# AudioXtreamer_Ymh01x.net
KiCad netlist of a schematic drawn in EAGLE
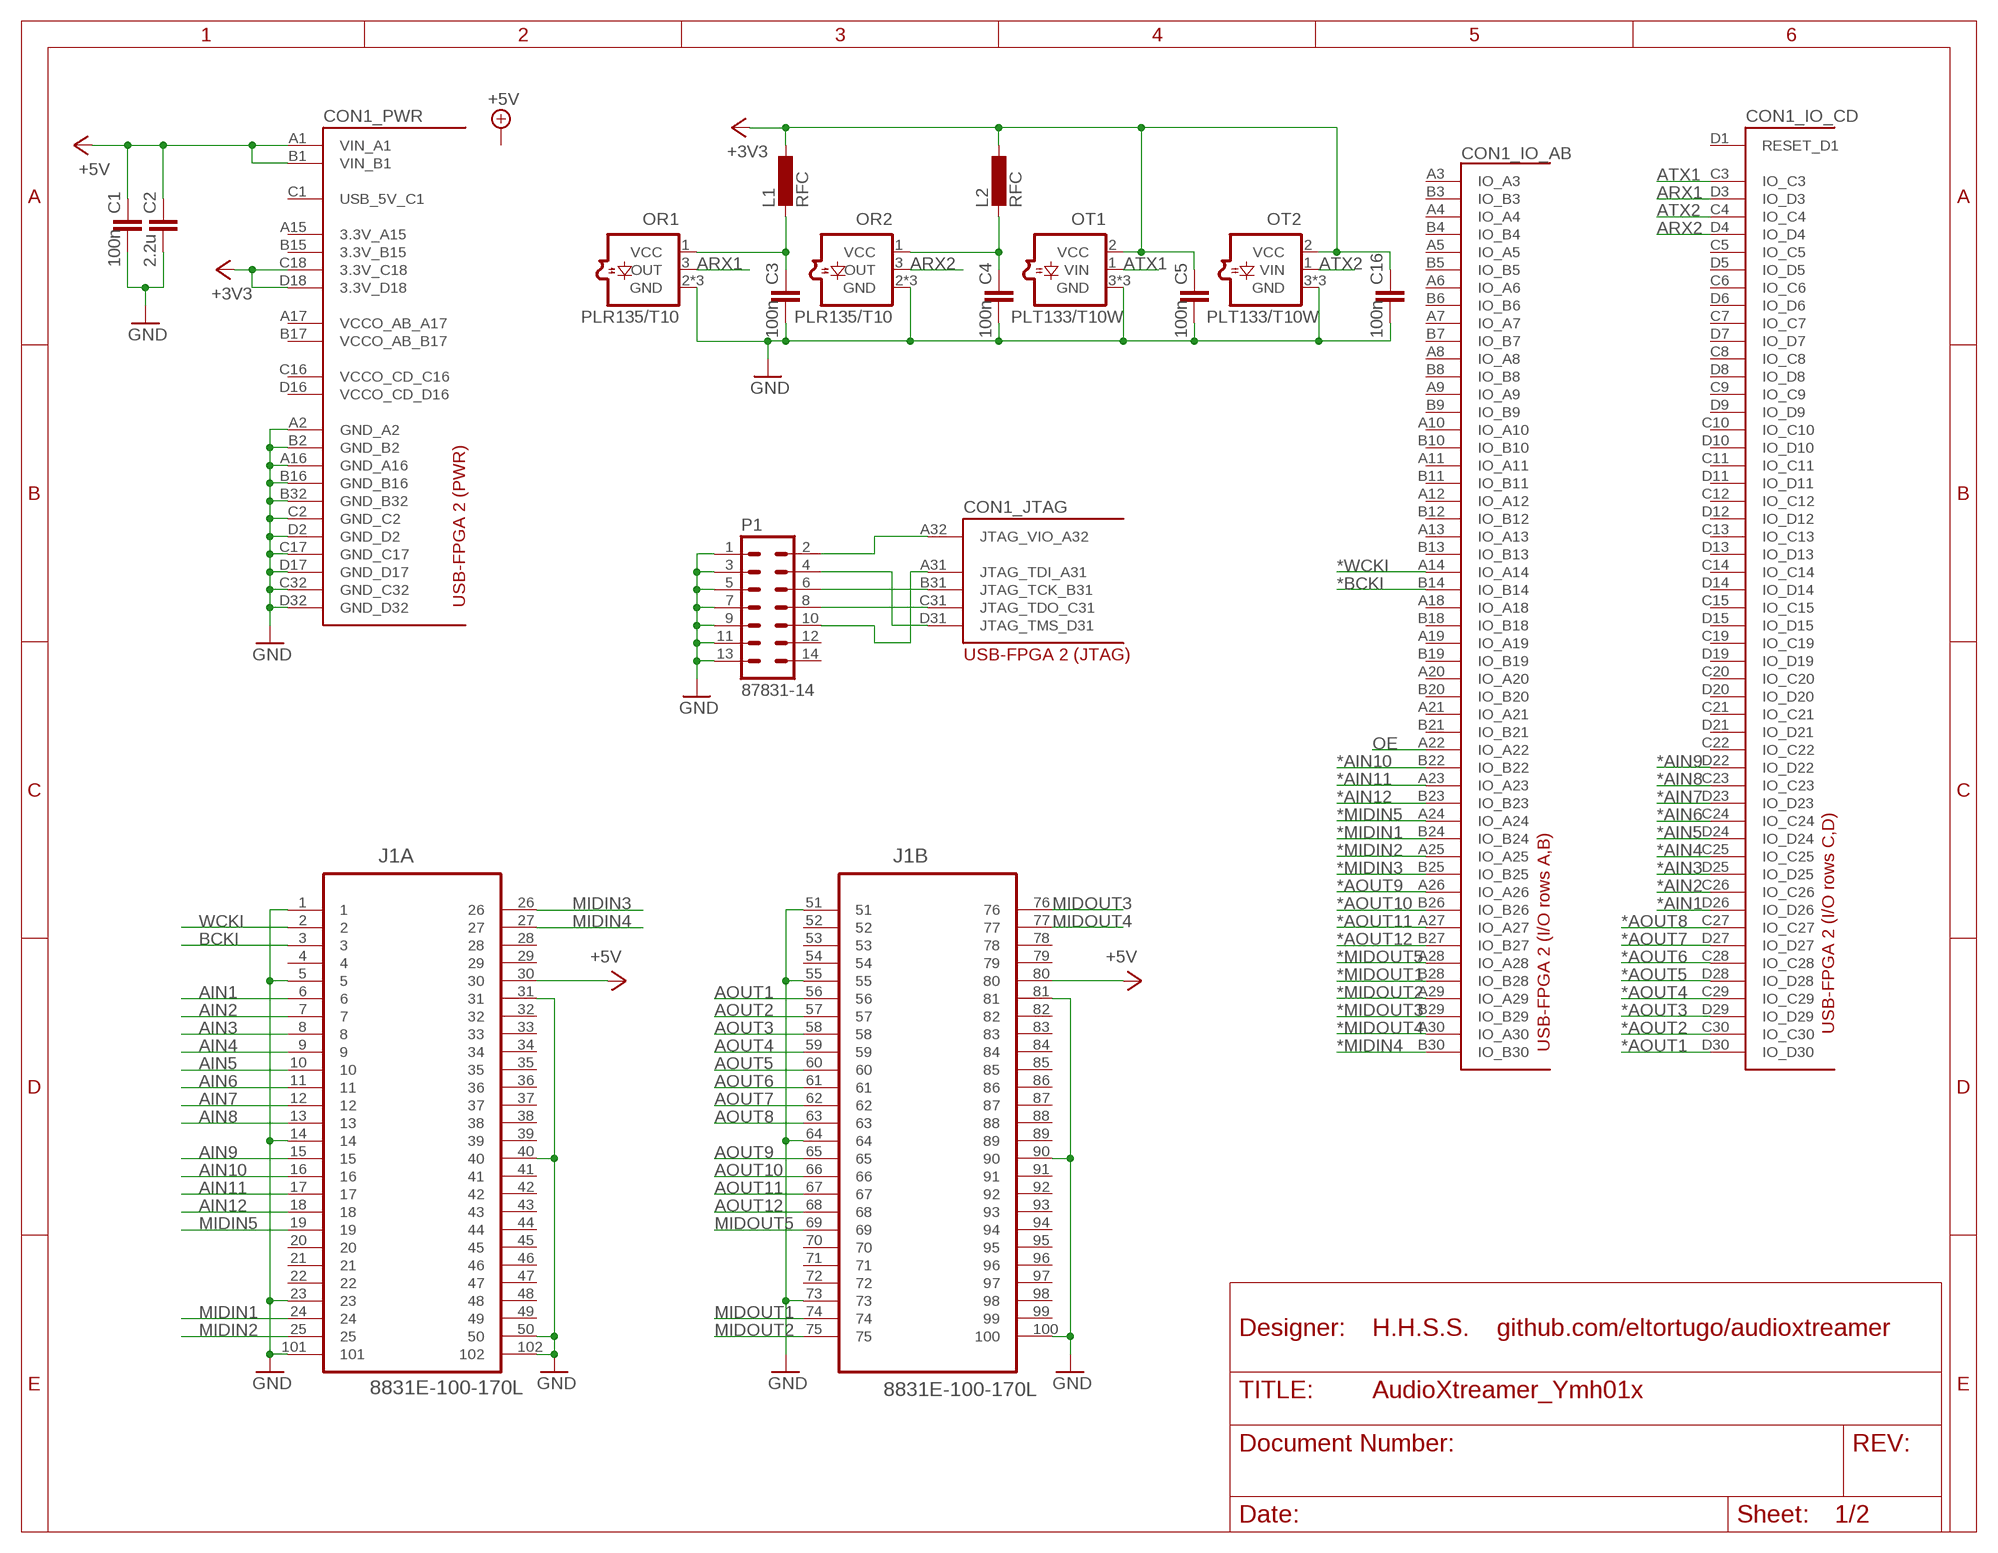
[diagram p0: schematic, sheet 1]
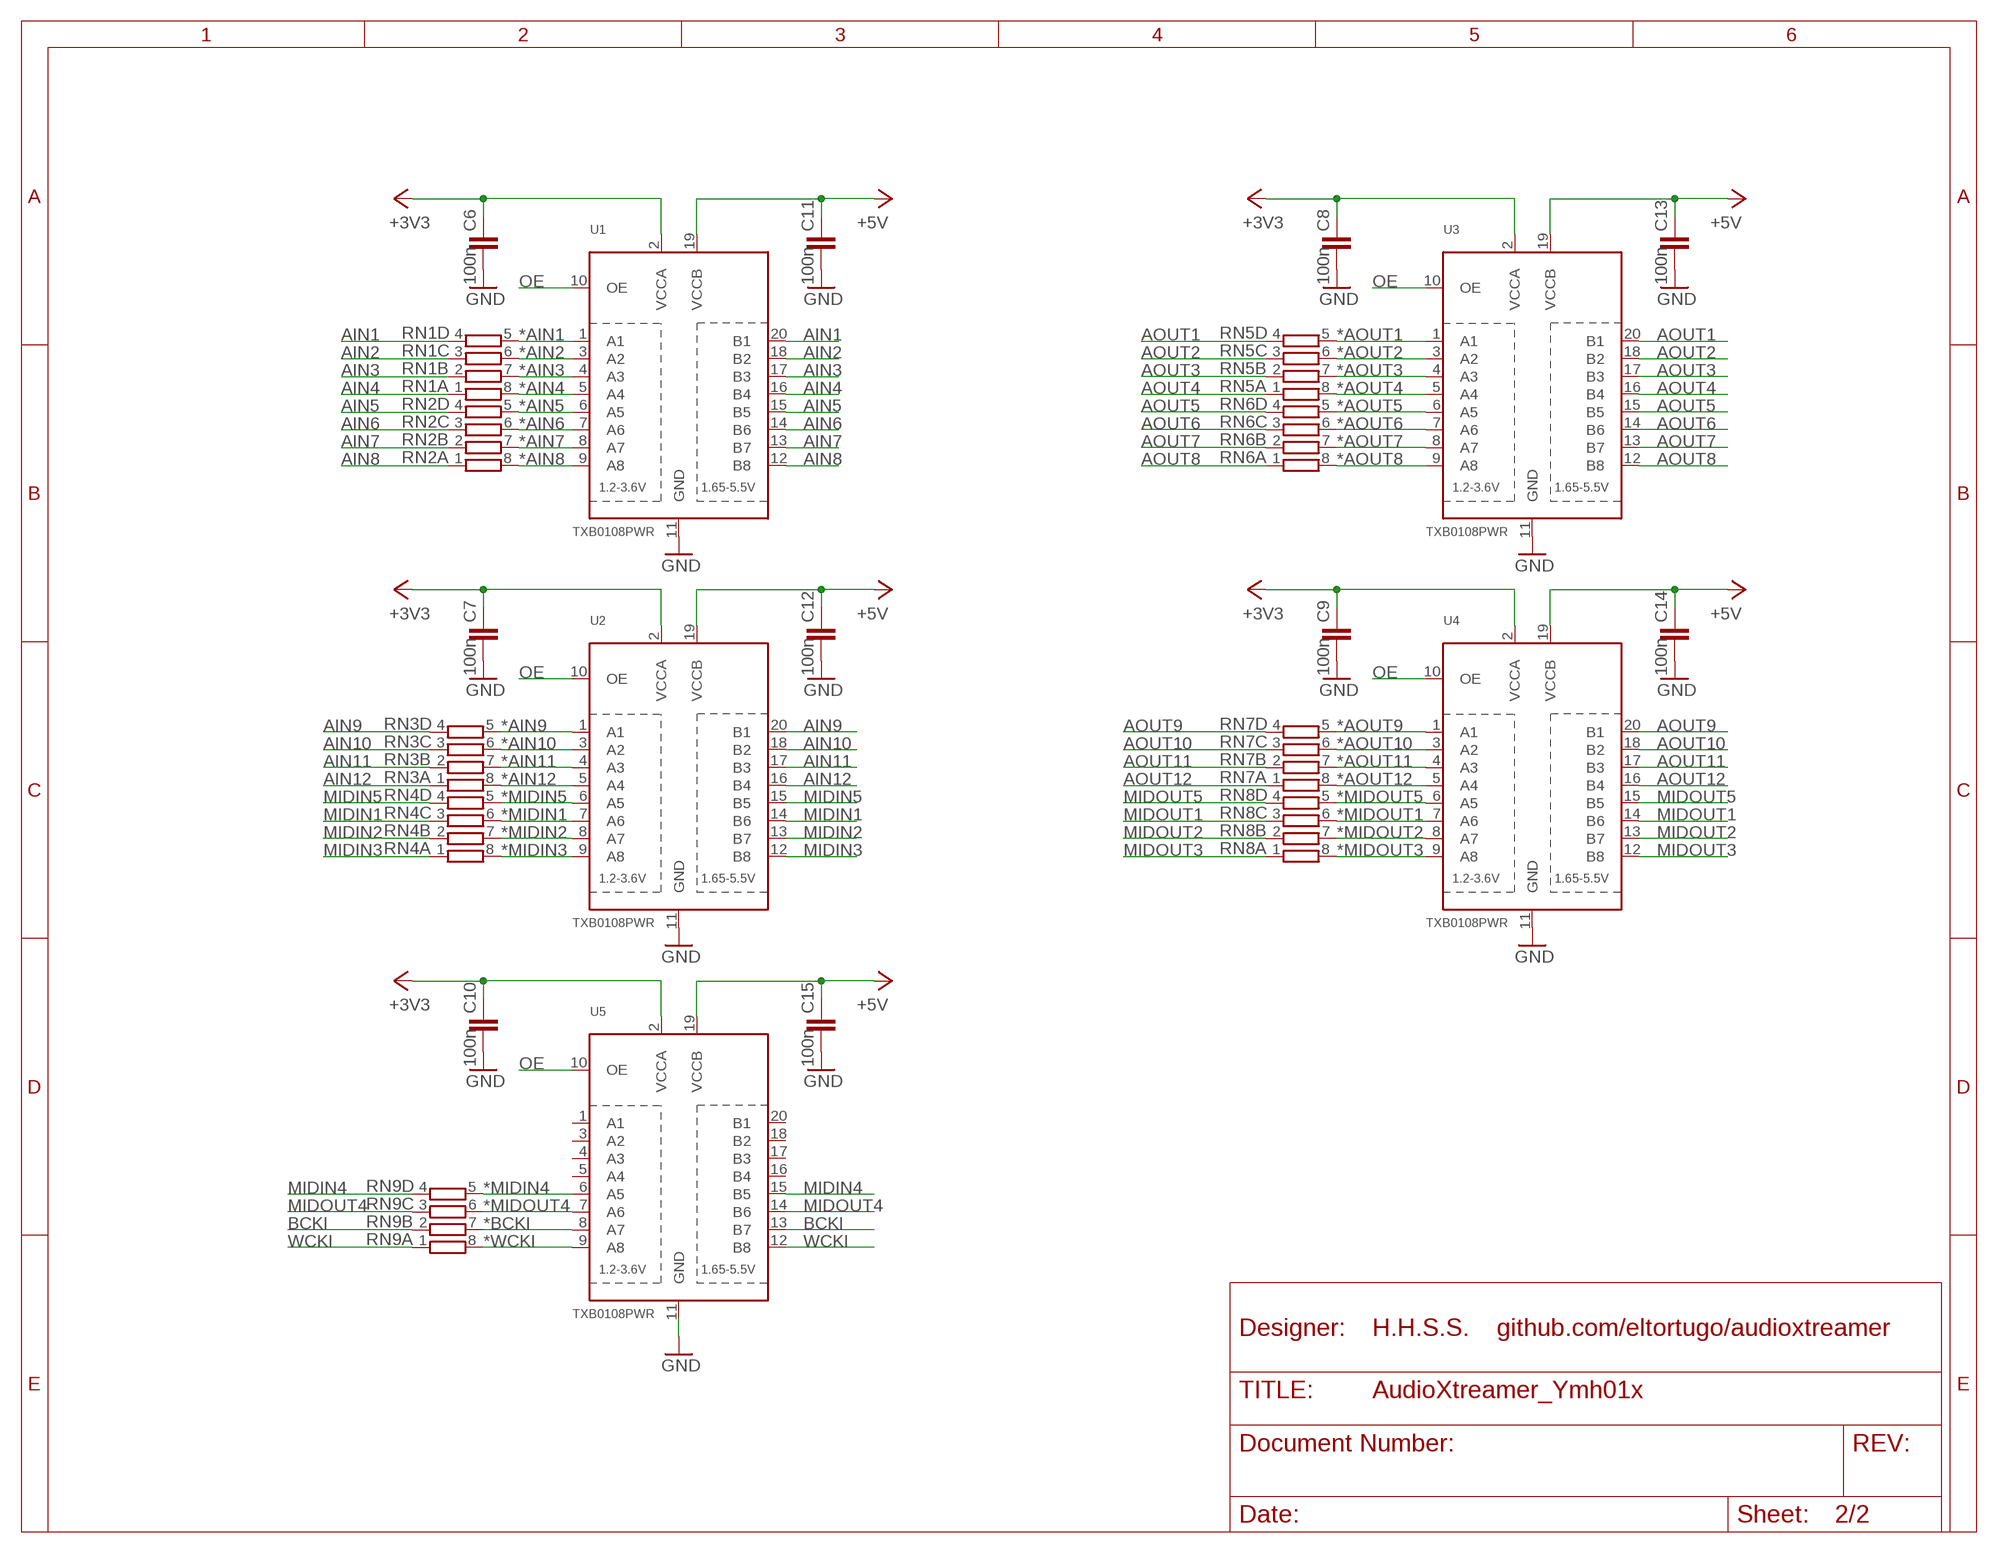
[diagram p1: schematic, sheet 2]

(export (version "E")
  (design (tool "Eeschema 10.0.6"))
  (components
    (comp (ref "C1")
      (value "100n")
      (footprint "eagle-import:C0603")
      (libsource (lib "eagle-import") (part "C-EUC0603"))
    )
    (comp (ref "C2")
      (value "2.2u")
      (footprint "eagle-import:C0603")
      (libsource (lib "eagle-import") (part "C-EUC0603"))
    )
    (comp (ref "C3")
      (value "100n")
      (footprint "eagle-import:C0603")
      (libsource (lib "eagle-import") (part "C-EUC0603"))
    )
    (comp (ref "C4")
      (value "100n")
      (footprint "eagle-import:C0603")
      (libsource (lib "eagle-import") (part "C-EUC0603"))
    )
    (comp (ref "C5")
      (value "100n")
      (footprint "eagle-import:C0603")
      (libsource (lib "eagle-import") (part "C-EUC0603"))
    )
    (comp (ref "C16")
      (value "100n")
      (footprint "eagle-import:C0603")
      (libsource (lib "eagle-import") (part "C-EUC0603"))
    )
    (comp (ref "CON1")
      (value "USB-FPGA-2THT")
      (footprint "eagle-import:USB-FPGA-2-THT")
      (libsource (lib "eagle-import") (part "USB-FPGA-2THT"))
    )
    (comp (ref "J1")
      (value "8831E-100-170L")
      (footprint "eagle-import:KEL_8831E-100-170L")
      (fields (field (name "MPN") "KEL_8831E-100-170L"))
      (libsource (lib "eagle-import") (part "8831E-100-170L"))
    )
    (comp (ref "L1")
      (value "RFC")
      (footprint "eagle-import:L2012C")
      (libsource (lib "eagle-import") (part "L-EUL2012C"))
    )
    (comp (ref "L2")
      (value "RFC")
      (footprint "eagle-import:L2012C")
      (libsource (lib "eagle-import") (part "L-EUL2012C"))
    )
    (comp (ref "OR1")
      (value "PLR135/T10")
      (footprint "eagle-import:PLR135_T10")
      (libsource (lib "eagle-import") (part "PLR135/T10"))
    )
    (comp (ref "OR2")
      (value "PLR135/T10")
      (footprint "eagle-import:PLR135_T10")
      (libsource (lib "eagle-import") (part "PLR135/T10"))
    )
    (comp (ref "OT1")
      (value "PLT133/T10W")
      (footprint "eagle-import:PLT133_T10")
      (libsource (lib "eagle-import") (part "PLT133/T10W"))
    )
    (comp (ref "OT2")
      (value "PLT133/T10W")
      (footprint "eagle-import:PLT133_T10")
      (libsource (lib "eagle-import") (part "PLT133/T10W"))
    )
    (comp (ref "P1")
      (value "87831-14")
      (footprint "eagle-import:87831-14")
      (libsource (lib "eagle-import") (part "87831-14"))
    )
    (comp (ref "C6")
      (value "100n")
      (footprint "eagle-import:C0603")
      (libsource (lib "eagle-import") (part "C-EUC0603"))
    )
    (comp (ref "C7")
      (value "100n")
      (footprint "eagle-import:C0603")
      (libsource (lib "eagle-import") (part "C-EUC0603"))
    )
    (comp (ref "C8")
      (value "100n")
      (footprint "eagle-import:C0603")
      (libsource (lib "eagle-import") (part "C-EUC0603"))
    )
    (comp (ref "C9")
      (value "100n")
      (footprint "eagle-import:C0603")
      (libsource (lib "eagle-import") (part "C-EUC0603"))
    )
    (comp (ref "C10")
      (value "100n")
      (footprint "eagle-import:C0603")
      (libsource (lib "eagle-import") (part "C-EUC0603"))
    )
    (comp (ref "C11")
      (value "100n")
      (footprint "eagle-import:C0603")
      (libsource (lib "eagle-import") (part "C-EUC0603"))
    )
    (comp (ref "C12")
      (value "100n")
      (footprint "eagle-import:C0603")
      (libsource (lib "eagle-import") (part "C-EUC0603"))
    )
    (comp (ref "C13")
      (value "100n")
      (footprint "eagle-import:C0603")
      (libsource (lib "eagle-import") (part "C-EUC0603"))
    )
    (comp (ref "C14")
      (value "100n")
      (footprint "eagle-import:C0603")
      (libsource (lib "eagle-import") (part "C-EUC0603"))
    )
    (comp (ref "C15")
      (value "100n")
      (footprint "eagle-import:C0603")
      (libsource (lib "eagle-import") (part "C-EUC0603"))
    )
    (comp (ref "RN1")
      (value "4R-N0603-ARC")
      (footprint "eagle-import:0603-ARC")
      (libsource (lib "eagle-import") (part "4R-N0603-ARC"))
    )
    (comp (ref "RN2")
      (value "4R-N0603-ARC")
      (footprint "eagle-import:0603-ARC")
      (libsource (lib "eagle-import") (part "4R-N0603-ARC"))
    )
    (comp (ref "RN3")
      (value "4R-N0603-ARC")
      (footprint "eagle-import:0603-ARC")
      (libsource (lib "eagle-import") (part "4R-N0603-ARC"))
    )
    (comp (ref "RN4")
      (value "4R-N0603-ARC")
      (footprint "eagle-import:0603-ARC")
      (libsource (lib "eagle-import") (part "4R-N0603-ARC"))
    )
    (comp (ref "RN5")
      (value "4R-N0603-ARC")
      (footprint "eagle-import:0603-ARC")
      (libsource (lib "eagle-import") (part "4R-N0603-ARC"))
    )
    (comp (ref "RN6")
      (value "4R-N0603-ARC")
      (footprint "eagle-import:0603-ARC")
      (libsource (lib "eagle-import") (part "4R-N0603-ARC"))
    )
    (comp (ref "RN7")
      (value "4R-N0603-ARC")
      (footprint "eagle-import:0603-ARC")
      (libsource (lib "eagle-import") (part "4R-N0603-ARC"))
    )
    (comp (ref "RN8")
      (value "4R-N0603-ARC")
      (footprint "eagle-import:0603-ARC")
      (libsource (lib "eagle-import") (part "4R-N0603-ARC"))
    )
    (comp (ref "RN9")
      (value "4R-N0603-ARC")
      (footprint "eagle-import:0603-ARC")
      (libsource (lib "eagle-import") (part "4R-N0603-ARC"))
    )
    (comp (ref "U1")
      (value "TXB0108PWR")
      (footprint "eagle-import:TSSOP20")
      (libsource (lib "eagle-import") (part "TXB0108PWR"))
    )
    (comp (ref "U2")
      (value "TXB0108PWR")
      (footprint "eagle-import:TSSOP20")
      (libsource (lib "eagle-import") (part "TXB0108PWR"))
    )
    (comp (ref "U3")
      (value "TXB0108PWR")
      (footprint "eagle-import:TSSOP20")
      (libsource (lib "eagle-import") (part "TXB0108PWR"))
    )
    (comp (ref "U4")
      (value "TXB0108PWR")
      (footprint "eagle-import:TSSOP20")
      (libsource (lib "eagle-import") (part "TXB0108PWR"))
    )
    (comp (ref "U5")
      (value "TXB0108PWR")
      (footprint "eagle-import:TSSOP20")
      (libsource (lib "eagle-import") (part "TXB0108PWR"))
    )
  )
  (nets
    (net (code "1") (name "*AIN1") (class "Default")
      (node (ref "CON1") (pin "D26") (pinfunction "IO_D26_D26") (pintype "bidirectional"))
      (node (ref "RN1") (pin "5") (pinfunction "2_5") (pintype "passive"))
      (node (ref "U1") (pin "1") (pinfunction "A1_1") (pintype "bidirectional"))
    )
    (net (code "2") (name "*AIN2") (class "Default")
      (node (ref "CON1") (pin "C26") (pinfunction "IO_C26_C26") (pintype "bidirectional"))
      (node (ref "RN1") (pin "6") (pinfunction "2_6") (pintype "passive"))
      (node (ref "U1") (pin "3") (pinfunction "A2_3") (pintype "bidirectional"))
    )
    (net (code "3") (name "*AIN3") (class "Default")
      (node (ref "CON1") (pin "D25") (pinfunction "IO_D25_D25") (pintype "bidirectional"))
      (node (ref "RN1") (pin "7") (pinfunction "2_7") (pintype "passive"))
      (node (ref "U1") (pin "4") (pinfunction "A3_4") (pintype "bidirectional"))
    )
    (net (code "4") (name "*AIN4") (class "Default")
      (node (ref "CON1") (pin "C25") (pinfunction "IO_C25_C25") (pintype "bidirectional"))
      (node (ref "RN1") (pin "8") (pinfunction "2_8") (pintype "passive"))
      (node (ref "U1") (pin "5") (pinfunction "A4_5") (pintype "bidirectional"))
    )
    (net (code "5") (name "*AIN5") (class "Default")
      (node (ref "CON1") (pin "D24") (pinfunction "IO_D24_D24") (pintype "bidirectional"))
      (node (ref "RN2") (pin "5") (pinfunction "2_5") (pintype "passive"))
      (node (ref "U1") (pin "6") (pinfunction "A5_6") (pintype "bidirectional"))
    )
    (net (code "6") (name "*AIN6") (class "Default")
      (node (ref "CON1") (pin "C24") (pinfunction "IO_C24_C24") (pintype "bidirectional"))
      (node (ref "RN2") (pin "6") (pinfunction "2_6") (pintype "passive"))
      (node (ref "U1") (pin "7") (pinfunction "A6_7") (pintype "bidirectional"))
    )
    (net (code "7") (name "*AIN7") (class "Default")
      (node (ref "CON1") (pin "D23") (pinfunction "IO_D23_D23") (pintype "bidirectional"))
      (node (ref "RN2") (pin "7") (pinfunction "2_7") (pintype "passive"))
      (node (ref "U1") (pin "8") (pinfunction "A7_8") (pintype "bidirectional"))
    )
    (net (code "8") (name "*AIN8") (class "Default")
      (node (ref "CON1") (pin "C23") (pinfunction "IO_C23_C23") (pintype "bidirectional"))
      (node (ref "RN2") (pin "8") (pinfunction "2_8") (pintype "passive"))
      (node (ref "U1") (pin "9") (pinfunction "A8_9") (pintype "bidirectional"))
    )
    (net (code "9") (name "*AIN9") (class "Default")
      (node (ref "CON1") (pin "D22") (pinfunction "IO_D22_D22") (pintype "bidirectional"))
      (node (ref "RN3") (pin "5") (pinfunction "2_5") (pintype "passive"))
      (node (ref "U2") (pin "1") (pinfunction "A1_1") (pintype "bidirectional"))
    )
    (net (code "10") (name "*AIN10") (class "Default")
      (node (ref "CON1") (pin "B22") (pinfunction "IO_B22_B22") (pintype "bidirectional"))
      (node (ref "RN3") (pin "6") (pinfunction "2_6") (pintype "passive"))
      (node (ref "U2") (pin "3") (pinfunction "A2_3") (pintype "bidirectional"))
    )
    (net (code "11") (name "*AIN11") (class "Default")
      (node (ref "CON1") (pin "A23") (pinfunction "IO_A23_A23") (pintype "bidirectional"))
      (node (ref "RN3") (pin "7") (pinfunction "2_7") (pintype "passive"))
      (node (ref "U2") (pin "4") (pinfunction "A3_4") (pintype "bidirectional"))
    )
    (net (code "12") (name "*AIN12") (class "Default")
      (node (ref "CON1") (pin "B23") (pinfunction "IO_B23_B23") (pintype "bidirectional"))
      (node (ref "RN3") (pin "8") (pinfunction "2_8") (pintype "passive"))
      (node (ref "U2") (pin "5") (pinfunction "A4_5") (pintype "bidirectional"))
    )
    (net (code "13") (name "*AOUT1") (class "Default")
      (node (ref "CON1") (pin "D30") (pinfunction "IO_D30_D30") (pintype "bidirectional"))
      (node (ref "RN5") (pin "5") (pinfunction "2_5") (pintype "passive"))
      (node (ref "U3") (pin "1") (pinfunction "A1_1") (pintype "bidirectional"))
    )
    (net (code "14") (name "*AOUT2") (class "Default")
      (node (ref "CON1") (pin "C30") (pinfunction "IO_C30_C30") (pintype "bidirectional"))
      (node (ref "RN5") (pin "6") (pinfunction "2_6") (pintype "passive"))
      (node (ref "U3") (pin "3") (pinfunction "A2_3") (pintype "bidirectional"))
    )
    (net (code "15") (name "*AOUT3") (class "Default")
      (node (ref "CON1") (pin "D29") (pinfunction "IO_D29_D29") (pintype "bidirectional"))
      (node (ref "RN5") (pin "7") (pinfunction "2_7") (pintype "passive"))
      (node (ref "U3") (pin "4") (pinfunction "A3_4") (pintype "bidirectional"))
    )
    (net (code "16") (name "*AOUT4") (class "Default")
      (node (ref "CON1") (pin "C29") (pinfunction "IO_C29_C29") (pintype "bidirectional"))
      (node (ref "RN5") (pin "8") (pinfunction "2_8") (pintype "passive"))
      (node (ref "U3") (pin "5") (pinfunction "A4_5") (pintype "bidirectional"))
    )
    (net (code "17") (name "*AOUT5") (class "Default")
      (node (ref "CON1") (pin "D28") (pinfunction "IO_D28_D28") (pintype "bidirectional"))
      (node (ref "RN6") (pin "5") (pinfunction "2_5") (pintype "passive"))
      (node (ref "U3") (pin "6") (pinfunction "A5_6") (pintype "bidirectional"))
    )
    (net (code "18") (name "*AOUT6") (class "Default")
      (node (ref "CON1") (pin "C28") (pinfunction "IO_C28_C28") (pintype "bidirectional"))
      (node (ref "RN6") (pin "6") (pinfunction "2_6") (pintype "passive"))
      (node (ref "U3") (pin "7") (pinfunction "A6_7") (pintype "bidirectional"))
    )
    (net (code "19") (name "*AOUT7") (class "Default")
      (node (ref "CON1") (pin "D27") (pinfunction "IO_D27_D27") (pintype "bidirectional"))
      (node (ref "RN6") (pin "7") (pinfunction "2_7") (pintype "passive"))
      (node (ref "U3") (pin "8") (pinfunction "A7_8") (pintype "bidirectional"))
    )
    (net (code "20") (name "*AOUT8") (class "Default")
      (node (ref "CON1") (pin "C27") (pinfunction "IO_C27_C27") (pintype "bidirectional"))
      (node (ref "RN6") (pin "8") (pinfunction "2_8") (pintype "passive"))
      (node (ref "U3") (pin "9") (pinfunction "A8_9") (pintype "bidirectional"))
    )
    (net (code "21") (name "*AOUT9") (class "Default")
      (node (ref "CON1") (pin "A26") (pinfunction "IO_A26_A26") (pintype "bidirectional"))
      (node (ref "RN7") (pin "5") (pinfunction "2_5") (pintype "passive"))
      (node (ref "U4") (pin "1") (pinfunction "A1_1") (pintype "bidirectional"))
    )
    (net (code "22") (name "*AOUT10") (class "Default")
      (node (ref "CON1") (pin "B26") (pinfunction "IO_B26_B26") (pintype "bidirectional"))
      (node (ref "RN7") (pin "6") (pinfunction "2_6") (pintype "passive"))
      (node (ref "U4") (pin "3") (pinfunction "A2_3") (pintype "bidirectional"))
    )
    (net (code "23") (name "*AOUT11") (class "Default")
      (node (ref "CON1") (pin "A27") (pinfunction "IO_A27_A27") (pintype "bidirectional"))
      (node (ref "RN7") (pin "7") (pinfunction "2_7") (pintype "passive"))
      (node (ref "U4") (pin "4") (pinfunction "A3_4") (pintype "bidirectional"))
    )
    (net (code "24") (name "*AOUT12") (class "Default")
      (node (ref "CON1") (pin "B27") (pinfunction "IO_B27_B27") (pintype "bidirectional"))
      (node (ref "RN7") (pin "8") (pinfunction "2_8") (pintype "passive"))
      (node (ref "U4") (pin "5") (pinfunction "A4_5") (pintype "bidirectional"))
    )
    (net (code "25") (name "*BCKI") (class "Default")
      (node (ref "CON1") (pin "B14") (pinfunction "IO_B14_B14") (pintype "bidirectional"))
      (node (ref "RN9") (pin "7") (pinfunction "2_7") (pintype "passive"))
      (node (ref "U5") (pin "8") (pinfunction "A7_8") (pintype "bidirectional"))
    )
    (net (code "26") (name "*MIDIN1") (class "Default")
      (node (ref "CON1") (pin "B24") (pinfunction "IO_B24_B24") (pintype "bidirectional"))
      (node (ref "RN4") (pin "6") (pinfunction "2_6") (pintype "passive"))
      (node (ref "U2") (pin "7") (pinfunction "A6_7") (pintype "bidirectional"))
    )
    (net (code "27") (name "*MIDIN2") (class "Default")
      (node (ref "CON1") (pin "A25") (pinfunction "IO_A25_A25") (pintype "bidirectional"))
      (node (ref "RN4") (pin "7") (pinfunction "2_7") (pintype "passive"))
      (node (ref "U2") (pin "8") (pinfunction "A7_8") (pintype "bidirectional"))
    )
    (net (code "28") (name "*MIDIN3") (class "Default")
      (node (ref "CON1") (pin "B25") (pinfunction "IO_B25_B25") (pintype "bidirectional"))
      (node (ref "RN4") (pin "8") (pinfunction "2_8") (pintype "passive"))
      (node (ref "U2") (pin "9") (pinfunction "A8_9") (pintype "bidirectional"))
    )
    (net (code "29") (name "*MIDIN4") (class "Default")
      (node (ref "CON1") (pin "B30") (pinfunction "IO_B30_B30") (pintype "bidirectional"))
      (node (ref "RN9") (pin "5") (pinfunction "2_5") (pintype "passive"))
      (node (ref "U5") (pin "6") (pinfunction "A5_6") (pintype "bidirectional"))
    )
    (net (code "30") (name "*MIDIN5") (class "Default")
      (node (ref "CON1") (pin "A24") (pinfunction "IO_A24_A24") (pintype "bidirectional"))
      (node (ref "RN4") (pin "5") (pinfunction "2_5") (pintype "passive"))
      (node (ref "U2") (pin "6") (pinfunction "A5_6") (pintype "bidirectional"))
    )
    (net (code "31") (name "*MIDOUT1") (class "Default")
      (node (ref "CON1") (pin "B28") (pinfunction "IO_B28_B28") (pintype "bidirectional"))
      (node (ref "RN8") (pin "6") (pinfunction "2_6") (pintype "passive"))
      (node (ref "U4") (pin "7") (pinfunction "A6_7") (pintype "bidirectional"))
    )
    (net (code "32") (name "*MIDOUT2") (class "Default")
      (node (ref "CON1") (pin "A29") (pinfunction "IO_A29_A29") (pintype "bidirectional"))
      (node (ref "RN8") (pin "7") (pinfunction "2_7") (pintype "passive"))
      (node (ref "U4") (pin "8") (pinfunction "A7_8") (pintype "bidirectional"))
    )
    (net (code "33") (name "*MIDOUT3") (class "Default")
      (node (ref "CON1") (pin "B29") (pinfunction "IO_B29_B29") (pintype "bidirectional"))
      (node (ref "RN8") (pin "8") (pinfunction "2_8") (pintype "passive"))
      (node (ref "U4") (pin "9") (pinfunction "A8_9") (pintype "bidirectional"))
    )
    (net (code "34") (name "*MIDOUT4") (class "Default")
      (node (ref "CON1") (pin "A30") (pinfunction "IO_A30_A30") (pintype "bidirectional"))
      (node (ref "RN9") (pin "6") (pinfunction "2_6") (pintype "passive"))
      (node (ref "U5") (pin "7") (pinfunction "A6_7") (pintype "bidirectional"))
    )
    (net (code "35") (name "*MIDOUT5") (class "Default")
      (node (ref "CON1") (pin "A28") (pinfunction "IO_A28_A28") (pintype "bidirectional"))
      (node (ref "RN8") (pin "5") (pinfunction "2_5") (pintype "passive"))
      (node (ref "U4") (pin "6") (pinfunction "A5_6") (pintype "bidirectional"))
    )
    (net (code "36") (name "*WCKI") (class "Default")
      (node (ref "CON1") (pin "A14") (pinfunction "IO_A14_A14") (pintype "bidirectional"))
      (node (ref "RN9") (pin "8") (pinfunction "2_8") (pintype "passive"))
      (node (ref "U5") (pin "9") (pinfunction "A8_9") (pintype "bidirectional"))
    )
    (net (code "37") (name "+3V3") (class "Default")
      (node (ref "C10") (pin "1") (pinfunction "1_1") (pintype "passive"))
      (node (ref "C16") (pin "1") (pinfunction "1_1") (pintype "passive"))
      (node (ref "C5") (pin "1") (pinfunction "1_1") (pintype "passive"))
      (node (ref "C6") (pin "1") (pinfunction "1_1") (pintype "passive"))
      (node (ref "C7") (pin "1") (pinfunction "1_1") (pintype "passive"))
      (node (ref "C8") (pin "1") (pinfunction "1_1") (pintype "passive"))
      (node (ref "C9") (pin "1") (pinfunction "1_1") (pintype "passive"))
      (node (ref "CON1") (pin "C18") (pinfunction "3.3V_C18_C18") (pintype "bidirectional"))
      (node (ref "CON1") (pin "D18") (pinfunction "3.3V_D18_D18") (pintype "bidirectional"))
      (node (ref "L1") (pin "1") (pinfunction "1_1") (pintype "passive"))
      (node (ref "L2") (pin "1") (pinfunction "1_1") (pintype "passive"))
      (node (ref "OT1") (pin "2") (pinfunction "VCC_2") (pintype "power_in"))
      (node (ref "OT2") (pin "2") (pinfunction "VCC_2") (pintype "power_in"))
      (node (ref "U1") (pin "2") (pinfunction "VCCA_2") (pintype "bidirectional"))
      (node (ref "U2") (pin "2") (pinfunction "VCCA_2") (pintype "bidirectional"))
      (node (ref "U3") (pin "2") (pinfunction "VCCA_2") (pintype "bidirectional"))
      (node (ref "U4") (pin "2") (pinfunction "VCCA_2") (pintype "bidirectional"))
      (node (ref "U5") (pin "2") (pinfunction "VCCA_2") (pintype "bidirectional"))
    )
    (net (code "38") (name "+5V") (class "Default")
      (node (ref "C1") (pin "1") (pinfunction "1_1") (pintype "passive"))
      (node (ref "C11") (pin "1") (pinfunction "1_1") (pintype "passive"))
      (node (ref "C12") (pin "1") (pinfunction "1_1") (pintype "passive"))
      (node (ref "C13") (pin "1") (pinfunction "1_1") (pintype "passive"))
      (node (ref "C14") (pin "1") (pinfunction "1_1") (pintype "passive"))
      (node (ref "C15") (pin "1") (pinfunction "1_1") (pintype "passive"))
      (node (ref "C2") (pin "1") (pinfunction "1_1") (pintype "passive"))
      (node (ref "CON1") (pin "A1") (pinfunction "VIN_A1_A1") (pintype "bidirectional"))
      (node (ref "CON1") (pin "B1") (pinfunction "VIN_B1_B1") (pintype "bidirectional"))
      (node (ref "J1") (pin "30") (pinfunction "30_30") (pintype "passive"))
      (node (ref "J1") (pin "80") (pinfunction "80_80") (pintype "passive"))
      (node (ref "U1") (pin "19") (pinfunction "VCCB_19") (pintype "bidirectional"))
      (node (ref "U2") (pin "19") (pinfunction "VCCB_19") (pintype "bidirectional"))
      (node (ref "U3") (pin "19") (pinfunction "VCCB_19") (pintype "bidirectional"))
      (node (ref "U4") (pin "19") (pinfunction "VCCB_19") (pintype "bidirectional"))
      (node (ref "U5") (pin "19") (pinfunction "VCCB_19") (pintype "bidirectional"))
    )
    (net (code "39") (name "AIN1") (class "Default")
      (node (ref "J1") (pin "6") (pinfunction "6_6") (pintype "passive"))
      (node (ref "RN1") (pin "4") (pinfunction "1_4") (pintype "passive"))
      (node (ref "U1") (pin "20") (pinfunction "B1_20") (pintype "bidirectional"))
    )
    (net (code "40") (name "AIN2") (class "Default")
      (node (ref "J1") (pin "7") (pinfunction "7_7") (pintype "passive"))
      (node (ref "RN1") (pin "3") (pinfunction "1_3") (pintype "passive"))
      (node (ref "U1") (pin "18") (pinfunction "B2_18") (pintype "bidirectional"))
    )
    (net (code "41") (name "AIN3") (class "Default")
      (node (ref "J1") (pin "8") (pinfunction "8_8") (pintype "passive"))
      (node (ref "RN1") (pin "2") (pinfunction "1_2") (pintype "passive"))
      (node (ref "U1") (pin "17") (pinfunction "B3_17") (pintype "bidirectional"))
    )
    (net (code "42") (name "AIN4") (class "Default")
      (node (ref "J1") (pin "9") (pinfunction "9_9") (pintype "passive"))
      (node (ref "RN1") (pin "1") (pinfunction "1_1") (pintype "passive"))
      (node (ref "U1") (pin "16") (pinfunction "B4_16") (pintype "bidirectional"))
    )
    (net (code "43") (name "AIN5") (class "Default")
      (node (ref "J1") (pin "10") (pinfunction "10_10") (pintype "passive"))
      (node (ref "RN2") (pin "4") (pinfunction "1_4") (pintype "passive"))
      (node (ref "U1") (pin "15") (pinfunction "B5_15") (pintype "bidirectional"))
    )
    (net (code "44") (name "AIN6") (class "Default")
      (node (ref "J1") (pin "11") (pinfunction "11_11") (pintype "passive"))
      (node (ref "RN2") (pin "3") (pinfunction "1_3") (pintype "passive"))
      (node (ref "U1") (pin "14") (pinfunction "B6_14") (pintype "bidirectional"))
    )
    (net (code "45") (name "AIN7") (class "Default")
      (node (ref "J1") (pin "12") (pinfunction "12_12") (pintype "passive"))
      (node (ref "RN2") (pin "2") (pinfunction "1_2") (pintype "passive"))
      (node (ref "U1") (pin "13") (pinfunction "B7_13") (pintype "bidirectional"))
    )
    (net (code "46") (name "AIN8") (class "Default")
      (node (ref "J1") (pin "13") (pinfunction "13_13") (pintype "passive"))
      (node (ref "RN2") (pin "1") (pinfunction "1_1") (pintype "passive"))
      (node (ref "U1") (pin "12") (pinfunction "B8_12") (pintype "bidirectional"))
    )
    (net (code "47") (name "AIN9") (class "Default")
      (node (ref "J1") (pin "15") (pinfunction "15_15") (pintype "passive"))
      (node (ref "RN3") (pin "4") (pinfunction "1_4") (pintype "passive"))
      (node (ref "U2") (pin "20") (pinfunction "B1_20") (pintype "bidirectional"))
    )
    (net (code "48") (name "AIN10") (class "Default")
      (node (ref "J1") (pin "16") (pinfunction "16_16") (pintype "passive"))
      (node (ref "RN3") (pin "3") (pinfunction "1_3") (pintype "passive"))
      (node (ref "U2") (pin "18") (pinfunction "B2_18") (pintype "bidirectional"))
    )
    (net (code "49") (name "AIN11") (class "Default")
      (node (ref "J1") (pin "17") (pinfunction "17_17") (pintype "passive"))
      (node (ref "RN3") (pin "2") (pinfunction "1_2") (pintype "passive"))
      (node (ref "U2") (pin "17") (pinfunction "B3_17") (pintype "bidirectional"))
    )
    (net (code "50") (name "AIN12") (class "Default")
      (node (ref "J1") (pin "18") (pinfunction "18_18") (pintype "passive"))
      (node (ref "RN3") (pin "1") (pinfunction "1_1") (pintype "passive"))
      (node (ref "U2") (pin "16") (pinfunction "B4_16") (pintype "bidirectional"))
    )
    (net (code "51") (name "AOUT1") (class "Default")
      (node (ref "J1") (pin "56") (pinfunction "56_56") (pintype "passive"))
      (node (ref "RN5") (pin "4") (pinfunction "1_4") (pintype "passive"))
      (node (ref "U3") (pin "20") (pinfunction "B1_20") (pintype "bidirectional"))
    )
    (net (code "52") (name "AOUT2") (class "Default")
      (node (ref "J1") (pin "57") (pinfunction "57_57") (pintype "passive"))
      (node (ref "RN5") (pin "3") (pinfunction "1_3") (pintype "passive"))
      (node (ref "U3") (pin "18") (pinfunction "B2_18") (pintype "bidirectional"))
    )
    (net (code "53") (name "AOUT3") (class "Default")
      (node (ref "J1") (pin "58") (pinfunction "58_58") (pintype "passive"))
      (node (ref "RN5") (pin "2") (pinfunction "1_2") (pintype "passive"))
      (node (ref "U3") (pin "17") (pinfunction "B3_17") (pintype "bidirectional"))
    )
    (net (code "54") (name "AOUT4") (class "Default")
      (node (ref "J1") (pin "59") (pinfunction "59_59") (pintype "passive"))
      (node (ref "RN5") (pin "1") (pinfunction "1_1") (pintype "passive"))
      (node (ref "U3") (pin "16") (pinfunction "B4_16") (pintype "bidirectional"))
    )
    (net (code "55") (name "AOUT5") (class "Default")
      (node (ref "J1") (pin "60") (pinfunction "60_60") (pintype "passive"))
      (node (ref "RN6") (pin "4") (pinfunction "1_4") (pintype "passive"))
      (node (ref "U3") (pin "15") (pinfunction "B5_15") (pintype "bidirectional"))
    )
    (net (code "56") (name "AOUT6") (class "Default")
      (node (ref "J1") (pin "61") (pinfunction "61_61") (pintype "passive"))
      (node (ref "RN6") (pin "3") (pinfunction "1_3") (pintype "passive"))
      (node (ref "U3") (pin "14") (pinfunction "B6_14") (pintype "bidirectional"))
    )
    (net (code "57") (name "AOUT7") (class "Default")
      (node (ref "J1") (pin "62") (pinfunction "62_62") (pintype "passive"))
      (node (ref "RN6") (pin "2") (pinfunction "1_2") (pintype "passive"))
      (node (ref "U3") (pin "13") (pinfunction "B7_13") (pintype "bidirectional"))
    )
    (net (code "58") (name "AOUT8") (class "Default")
      (node (ref "J1") (pin "63") (pinfunction "63_63") (pintype "passive"))
      (node (ref "RN6") (pin "1") (pinfunction "1_1") (pintype "passive"))
      (node (ref "U3") (pin "12") (pinfunction "B8_12") (pintype "bidirectional"))
    )
    (net (code "59") (name "AOUT9") (class "Default")
      (node (ref "J1") (pin "65") (pinfunction "65_65") (pintype "passive"))
      (node (ref "RN7") (pin "4") (pinfunction "1_4") (pintype "passive"))
      (node (ref "U4") (pin "20") (pinfunction "B1_20") (pintype "bidirectional"))
    )
    (net (code "60") (name "AOUT10") (class "Default")
      (node (ref "J1") (pin "66") (pinfunction "66_66") (pintype "passive"))
      (node (ref "RN7") (pin "3") (pinfunction "1_3") (pintype "passive"))
      (node (ref "U4") (pin "18") (pinfunction "B2_18") (pintype "bidirectional"))
    )
    (net (code "61") (name "AOUT11") (class "Default")
      (node (ref "J1") (pin "67") (pinfunction "67_67") (pintype "passive"))
      (node (ref "RN7") (pin "2") (pinfunction "1_2") (pintype "passive"))
      (node (ref "U4") (pin "17") (pinfunction "B3_17") (pintype "bidirectional"))
    )
    (net (code "62") (name "AOUT12") (class "Default")
      (node (ref "J1") (pin "68") (pinfunction "68_68") (pintype "passive"))
      (node (ref "RN7") (pin "1") (pinfunction "1_1") (pintype "passive"))
      (node (ref "U4") (pin "16") (pinfunction "B4_16") (pintype "bidirectional"))
    )
    (net (code "63") (name "ARX1") (class "Default")
      (node (ref "CON1") (pin "D3") (pinfunction "IO_D3_D3") (pintype "bidirectional"))
      (node (ref "OR1") (pin "3") (pinfunction "OUT_3") (pintype "output"))
    )
    (net (code "64") (name "ARX2") (class "Default")
      (node (ref "CON1") (pin "D4") (pinfunction "IO_D4_D4") (pintype "bidirectional"))
      (node (ref "OR2") (pin "3") (pinfunction "OUT_3") (pintype "output"))
    )
    (net (code "65") (name "ATX1") (class "Default")
      (node (ref "CON1") (pin "C3") (pinfunction "IO_C3_C3") (pintype "bidirectional"))
      (node (ref "OT1") (pin "1") (pinfunction "VIN_1") (pintype "input"))
    )
    (net (code "66") (name "ATX2") (class "Default")
      (node (ref "CON1") (pin "C4") (pinfunction "IO_C4_C4") (pintype "bidirectional"))
      (node (ref "OT2") (pin "1") (pinfunction "VIN_1") (pintype "input"))
    )
    (net (code "67") (name "BCKI") (class "Default")
      (node (ref "J1") (pin "3") (pinfunction "3_3") (pintype "passive"))
      (node (ref "RN9") (pin "2") (pinfunction "1_2") (pintype "passive"))
      (node (ref "U5") (pin "13") (pinfunction "B7_13") (pintype "bidirectional"))
    )
    (net (code "68") (name "GND") (class "Default")
      (node (ref "C1") (pin "2") (pinfunction "2_2") (pintype "passive"))
      (node (ref "C10") (pin "2") (pinfunction "2_2") (pintype "passive"))
      (node (ref "C11") (pin "2") (pinfunction "2_2") (pintype "passive"))
      (node (ref "C12") (pin "2") (pinfunction "2_2") (pintype "passive"))
      (node (ref "C13") (pin "2") (pinfunction "2_2") (pintype "passive"))
      (node (ref "C14") (pin "2") (pinfunction "2_2") (pintype "passive"))
      (node (ref "C15") (pin "2") (pinfunction "2_2") (pintype "passive"))
      (node (ref "C16") (pin "2") (pinfunction "2_2") (pintype "passive"))
      (node (ref "C2") (pin "2") (pinfunction "2_2") (pintype "passive"))
      (node (ref "C3") (pin "2") (pinfunction "2_2") (pintype "passive"))
      (node (ref "C4") (pin "2") (pinfunction "2_2") (pintype "passive"))
      (node (ref "C5") (pin "2") (pinfunction "2_2") (pintype "passive"))
      (node (ref "C6") (pin "2") (pinfunction "2_2") (pintype "passive"))
      (node (ref "C7") (pin "2") (pinfunction "2_2") (pintype "passive"))
      (node (ref "C8") (pin "2") (pinfunction "2_2") (pintype "passive"))
      (node (ref "C9") (pin "2") (pinfunction "2_2") (pintype "passive"))
      (node (ref "CON1") (pin "A16") (pinfunction "GND_A16_A16") (pintype "bidirectional"))
      (node (ref "CON1") (pin "A2") (pinfunction "GND_A2_A2") (pintype "bidirectional"))
      (node (ref "CON1") (pin "B16") (pinfunction "GND_B16_B16") (pintype "bidirectional"))
      (node (ref "CON1") (pin "B2") (pinfunction "GND_B2_B2") (pintype "bidirectional"))
      (node (ref "CON1") (pin "B32") (pinfunction "GND_B32_B32") (pintype "bidirectional"))
      (node (ref "CON1") (pin "C17") (pinfunction "GND_C17_C17") (pintype "bidirectional"))
      (node (ref "CON1") (pin "C2") (pinfunction "GND_C2_C2") (pintype "bidirectional"))
      (node (ref "CON1") (pin "C32") (pinfunction "GND_C32_C32") (pintype "bidirectional"))
      (node (ref "CON1") (pin "D17") (pinfunction "GND_D17_D17") (pintype "bidirectional"))
      (node (ref "CON1") (pin "D2") (pinfunction "GND_D2_D2") (pintype "bidirectional"))
      (node (ref "CON1") (pin "D32") (pinfunction "GND_D32_D32") (pintype "bidirectional"))
      (node (ref "J1") (pin "1") (pinfunction "1_1") (pintype "passive"))
      (node (ref "J1") (pin "100") (pinfunction "100_100") (pintype "passive"))
      (node (ref "J1") (pin "101") (pinfunction "101_101") (pintype "passive"))
      (node (ref "J1") (pin "102") (pinfunction "102_102") (pintype "passive"))
      (node (ref "J1") (pin "14") (pinfunction "14_14") (pintype "passive"))
      (node (ref "J1") (pin "23") (pinfunction "23_23") (pintype "passive"))
      (node (ref "J1") (pin "31") (pinfunction "31_31") (pintype "passive"))
      (node (ref "J1") (pin "40") (pinfunction "40_40") (pintype "passive"))
      (node (ref "J1") (pin "5") (pinfunction "5_5") (pintype "passive"))
      (node (ref "J1") (pin "50") (pinfunction "50_50") (pintype "passive"))
      (node (ref "J1") (pin "51") (pinfunction "51_51") (pintype "passive"))
      (node (ref "J1") (pin "55") (pinfunction "55_55") (pintype "passive"))
      (node (ref "J1") (pin "64") (pinfunction "64_64") (pintype "passive"))
      (node (ref "J1") (pin "73") (pinfunction "73_73") (pintype "passive"))
      (node (ref "J1") (pin "81") (pinfunction "81_81") (pintype "passive"))
      (node (ref "J1") (pin "90") (pinfunction "90_90") (pintype "passive"))
      (node (ref "OR1") (pin "2") (pinfunction "GND_2") (pintype "power_in"))
      (node (ref "OR1") (pin "NC1") (pinfunction "GND_NC1") (pintype "power_in"))
      (node (ref "OR1") (pin "NC2") (pinfunction "GND_NC2") (pintype "power_in"))
      (node (ref "OR2") (pin "2") (pinfunction "GND_2") (pintype "power_in"))
      (node (ref "OR2") (pin "NC1") (pinfunction "GND_NC1") (pintype "power_in"))
      (node (ref "OR2") (pin "NC2") (pinfunction "GND_NC2") (pintype "power_in"))
      (node (ref "OT1") (pin "3") (pinfunction "GND_3") (pintype "power_in"))
      (node (ref "OT1") (pin "NC1") (pinfunction "GND_NC1") (pintype "power_in"))
      (node (ref "OT1") (pin "NC2") (pinfunction "GND_NC2") (pintype "power_in"))
      (node (ref "OT2") (pin "3") (pinfunction "GND_3") (pintype "power_in"))
      (node (ref "OT2") (pin "NC1") (pinfunction "GND_NC1") (pintype "power_in"))
      (node (ref "OT2") (pin "NC2") (pinfunction "GND_NC2") (pintype "power_in"))
      (node (ref "P1") (pin "1") (pinfunction "1_1") (pintype "passive"))
      (node (ref "P1") (pin "11") (pinfunction "11_11") (pintype "passive"))
      (node (ref "P1") (pin "13") (pinfunction "13_13") (pintype "passive"))
      (node (ref "P1") (pin "3") (pinfunction "3_3") (pintype "passive"))
      (node (ref "P1") (pin "5") (pinfunction "5_5") (pintype "passive"))
      (node (ref "P1") (pin "7") (pinfunction "7_7") (pintype "passive"))
      (node (ref "P1") (pin "9") (pinfunction "9_9") (pintype "passive"))
      (node (ref "U1") (pin "11") (pinfunction "GND_11") (pintype "bidirectional"))
      (node (ref "U2") (pin "11") (pinfunction "GND_11") (pintype "bidirectional"))
      (node (ref "U3") (pin "11") (pinfunction "GND_11") (pintype "bidirectional"))
      (node (ref "U4") (pin "11") (pinfunction "GND_11") (pintype "bidirectional"))
      (node (ref "U5") (pin "11") (pinfunction "GND_11") (pintype "bidirectional"))
    )
    (net (code "69") (name "MIDIN1") (class "Default")
      (node (ref "J1") (pin "24") (pinfunction "24_24") (pintype "passive"))
      (node (ref "RN4") (pin "3") (pinfunction "1_3") (pintype "passive"))
      (node (ref "U2") (pin "14") (pinfunction "B6_14") (pintype "bidirectional"))
    )
    (net (code "70") (name "MIDIN2") (class "Default")
      (node (ref "J1") (pin "25") (pinfunction "25_25") (pintype "passive"))
      (node (ref "RN4") (pin "2") (pinfunction "1_2") (pintype "passive"))
      (node (ref "U2") (pin "13") (pinfunction "B7_13") (pintype "bidirectional"))
    )
    (net (code "71") (name "MIDIN3") (class "Default")
      (node (ref "J1") (pin "26") (pinfunction "26_26") (pintype "passive"))
      (node (ref "RN4") (pin "1") (pinfunction "1_1") (pintype "passive"))
      (node (ref "U2") (pin "12") (pinfunction "B8_12") (pintype "bidirectional"))
    )
    (net (code "72") (name "MIDIN4") (class "Default")
      (node (ref "J1") (pin "27") (pinfunction "27_27") (pintype "passive"))
      (node (ref "RN9") (pin "4") (pinfunction "1_4") (pintype "passive"))
      (node (ref "U5") (pin "15") (pinfunction "B5_15") (pintype "bidirectional"))
    )
    (net (code "73") (name "MIDIN5") (class "Default")
      (node (ref "J1") (pin "19") (pinfunction "19_19") (pintype "passive"))
      (node (ref "RN4") (pin "4") (pinfunction "1_4") (pintype "passive"))
      (node (ref "U2") (pin "15") (pinfunction "B5_15") (pintype "bidirectional"))
    )
    (net (code "74") (name "MIDOUT1") (class "Default")
      (node (ref "J1") (pin "74") (pinfunction "74_74") (pintype "passive"))
      (node (ref "RN8") (pin "3") (pinfunction "1_3") (pintype "passive"))
      (node (ref "U4") (pin "14") (pinfunction "B6_14") (pintype "bidirectional"))
    )
    (net (code "75") (name "MIDOUT2") (class "Default")
      (node (ref "J1") (pin "75") (pinfunction "75_75") (pintype "passive"))
      (node (ref "RN8") (pin "2") (pinfunction "1_2") (pintype "passive"))
      (node (ref "U4") (pin "13") (pinfunction "B7_13") (pintype "bidirectional"))
    )
    (net (code "76") (name "MIDOUT3") (class "Default")
      (node (ref "J1") (pin "76") (pinfunction "76_76") (pintype "passive"))
      (node (ref "RN8") (pin "1") (pinfunction "1_1") (pintype "passive"))
      (node (ref "U4") (pin "12") (pinfunction "B8_12") (pintype "bidirectional"))
    )
    (net (code "77") (name "MIDOUT4") (class "Default")
      (node (ref "J1") (pin "77") (pinfunction "77_77") (pintype "passive"))
      (node (ref "RN9") (pin "3") (pinfunction "1_3") (pintype "passive"))
      (node (ref "U5") (pin "14") (pinfunction "B6_14") (pintype "bidirectional"))
    )
    (net (code "78") (name "MIDOUT5") (class "Default")
      (node (ref "J1") (pin "69") (pinfunction "69_69") (pintype "passive"))
      (node (ref "RN8") (pin "4") (pinfunction "1_4") (pintype "passive"))
      (node (ref "U4") (pin "15") (pinfunction "B5_15") (pintype "bidirectional"))
    )
    (net (code "79") (name "Net-(CON1C-JTAG_TCK_B31)") (class "Default")
      (node (ref "CON1") (pin "B31") (pinfunction "JTAG_TCK_B31_B31") (pintype "bidirectional"))
      (node (ref "P1") (pin "6") (pinfunction "6_6") (pintype "passive"))
    )
    (net (code "80") (name "Net-(CON1C-JTAG_TDI_A31)") (class "Default")
      (node (ref "CON1") (pin "A31") (pinfunction "JTAG_TDI_A31_A31") (pintype "bidirectional"))
      (node (ref "P1") (pin "10") (pinfunction "10_10") (pintype "passive"))
    )
    (net (code "81") (name "Net-(CON1C-JTAG_TDO_C31)") (class "Default")
      (node (ref "CON1") (pin "C31") (pinfunction "JTAG_TDO_C31_C31") (pintype "bidirectional"))
      (node (ref "P1") (pin "8") (pinfunction "8_8") (pintype "passive"))
    )
    (net (code "82") (name "Net-(CON1C-JTAG_TMS_D31)") (class "Default")
      (node (ref "CON1") (pin "D31") (pinfunction "JTAG_TMS_D31_D31") (pintype "bidirectional"))
      (node (ref "P1") (pin "4") (pinfunction "4_4") (pintype "passive"))
    )
    (net (code "83") (name "Net-(CON1C-JTAG_VIO_A32)") (class "Default")
      (node (ref "CON1") (pin "A32") (pinfunction "JTAG_VIO_A32_A32") (pintype "bidirectional"))
      (node (ref "P1") (pin "2") (pinfunction "2_2") (pintype "passive"))
    )
    (net (code "84") (name "Net-(OR1-VCC)") (class "Default")
      (node (ref "C3") (pin "1") (pinfunction "1_1") (pintype "passive"))
      (node (ref "L1") (pin "2") (pinfunction "2_2") (pintype "passive"))
      (node (ref "OR1") (pin "1") (pinfunction "VCC_1") (pintype "power_in"))
    )
    (net (code "85") (name "Net-(OR2-VCC)") (class "Default")
      (node (ref "C4") (pin "1") (pinfunction "1_1") (pintype "passive"))
      (node (ref "L2") (pin "2") (pinfunction "2_2") (pintype "passive"))
      (node (ref "OR2") (pin "1") (pinfunction "VCC_1") (pintype "power_in"))
    )
    (net (code "86") (name "OE") (class "Default")
      (node (ref "CON1") (pin "A22") (pinfunction "IO_A22_A22") (pintype "bidirectional"))
      (node (ref "U1") (pin "10") (pinfunction "OE_10") (pintype "bidirectional"))
      (node (ref "U2") (pin "10") (pinfunction "OE_10") (pintype "bidirectional"))
      (node (ref "U3") (pin "10") (pinfunction "OE_10") (pintype "bidirectional"))
      (node (ref "U4") (pin "10") (pinfunction "OE_10") (pintype "bidirectional"))
      (node (ref "U5") (pin "10") (pinfunction "OE_10") (pintype "bidirectional"))
    )
    (net (code "87") (name "WCKI") (class "Default")
      (node (ref "J1") (pin "2") (pinfunction "2_2") (pintype "passive"))
      (node (ref "RN9") (pin "1") (pinfunction "1_1") (pintype "passive"))
      (node (ref "U5") (pin "12") (pinfunction "B8_12") (pintype "bidirectional"))
    )
    (net (code "88") (name "unconnected-(CON1A-IO_A3-PadA3)") (class "Default")
      (node (ref "CON1") (pin "A3") (pinfunction "IO_A3_A3") (pintype "bidirectional"))
    )
    (net (code "89") (name "unconnected-(CON1A-IO_A4-PadA4)") (class "Default")
      (node (ref "CON1") (pin "A4") (pinfunction "IO_A4_A4") (pintype "bidirectional"))
    )
    (net (code "90") (name "unconnected-(CON1A-IO_A5-PadA5)") (class "Default")
      (node (ref "CON1") (pin "A5") (pinfunction "IO_A5_A5") (pintype "bidirectional"))
    )
    (net (code "91") (name "unconnected-(CON1A-IO_A6-PadA6)") (class "Default")
      (node (ref "CON1") (pin "A6") (pinfunction "IO_A6_A6") (pintype "bidirectional"))
    )
    (net (code "92") (name "unconnected-(CON1A-IO_A7-PadA7)") (class "Default")
      (node (ref "CON1") (pin "A7") (pinfunction "IO_A7_A7") (pintype "bidirectional"))
    )
    (net (code "93") (name "unconnected-(CON1A-IO_A8-PadA8)") (class "Default")
      (node (ref "CON1") (pin "A8") (pinfunction "IO_A8_A8") (pintype "bidirectional"))
    )
    (net (code "94") (name "unconnected-(CON1A-IO_A9-PadA9)") (class "Default")
      (node (ref "CON1") (pin "A9") (pinfunction "IO_A9_A9") (pintype "bidirectional"))
    )
    (net (code "95") (name "unconnected-(CON1A-IO_A10-PadA10)") (class "Default")
      (node (ref "CON1") (pin "A10") (pinfunction "IO_A10_A10") (pintype "bidirectional"))
    )
    (net (code "96") (name "unconnected-(CON1A-IO_A11-PadA11)") (class "Default")
      (node (ref "CON1") (pin "A11") (pinfunction "IO_A11_A11") (pintype "bidirectional"))
    )
    (net (code "97") (name "unconnected-(CON1A-IO_A12-PadA12)") (class "Default")
      (node (ref "CON1") (pin "A12") (pinfunction "IO_A12_A12") (pintype "bidirectional"))
    )
    (net (code "98") (name "unconnected-(CON1A-IO_A13-PadA13)") (class "Default")
      (node (ref "CON1") (pin "A13") (pinfunction "IO_A13_A13") (pintype "bidirectional"))
    )
    (net (code "99") (name "unconnected-(CON1A-IO_A18-PadA18)") (class "Default")
      (node (ref "CON1") (pin "A18") (pinfunction "IO_A18_A18") (pintype "bidirectional"))
    )
    (net (code "100") (name "unconnected-(CON1A-IO_A19-PadA19)") (class "Default")
      (node (ref "CON1") (pin "A19") (pinfunction "IO_A19_A19") (pintype "bidirectional"))
    )
    (net (code "101") (name "unconnected-(CON1A-IO_A20-PadA20)") (class "Default")
      (node (ref "CON1") (pin "A20") (pinfunction "IO_A20_A20") (pintype "bidirectional"))
    )
    (net (code "102") (name "unconnected-(CON1A-IO_A21-PadA21)") (class "Default")
      (node (ref "CON1") (pin "A21") (pinfunction "IO_A21_A21") (pintype "bidirectional"))
    )
    (net (code "103") (name "unconnected-(CON1A-IO_B3-PadB3)") (class "Default")
      (node (ref "CON1") (pin "B3") (pinfunction "IO_B3_B3") (pintype "bidirectional"))
    )
    (net (code "104") (name "unconnected-(CON1A-IO_B4-PadB4)") (class "Default")
      (node (ref "CON1") (pin "B4") (pinfunction "IO_B4_B4") (pintype "bidirectional"))
    )
    (net (code "105") (name "unconnected-(CON1A-IO_B5-PadB5)") (class "Default")
      (node (ref "CON1") (pin "B5") (pinfunction "IO_B5_B5") (pintype "bidirectional"))
    )
    (net (code "106") (name "unconnected-(CON1A-IO_B6-PadB6)") (class "Default")
      (node (ref "CON1") (pin "B6") (pinfunction "IO_B6_B6") (pintype "bidirectional"))
    )
    (net (code "107") (name "unconnected-(CON1A-IO_B7-PadB7)") (class "Default")
      (node (ref "CON1") (pin "B7") (pinfunction "IO_B7_B7") (pintype "bidirectional"))
    )
    (net (code "108") (name "unconnected-(CON1A-IO_B8-PadB8)") (class "Default")
      (node (ref "CON1") (pin "B8") (pinfunction "IO_B8_B8") (pintype "bidirectional"))
    )
    (net (code "109") (name "unconnected-(CON1A-IO_B9-PadB9)") (class "Default")
      (node (ref "CON1") (pin "B9") (pinfunction "IO_B9_B9") (pintype "bidirectional"))
    )
    (net (code "110") (name "unconnected-(CON1A-IO_B10-PadB10)") (class "Default")
      (node (ref "CON1") (pin "B10") (pinfunction "IO_B10_B10") (pintype "bidirectional"))
    )
    (net (code "111") (name "unconnected-(CON1A-IO_B11-PadB11)") (class "Default")
      (node (ref "CON1") (pin "B11") (pinfunction "IO_B11_B11") (pintype "bidirectional"))
    )
    (net (code "112") (name "unconnected-(CON1A-IO_B12-PadB12)") (class "Default")
      (node (ref "CON1") (pin "B12") (pinfunction "IO_B12_B12") (pintype "bidirectional"))
    )
    (net (code "113") (name "unconnected-(CON1A-IO_B13-PadB13)") (class "Default")
      (node (ref "CON1") (pin "B13") (pinfunction "IO_B13_B13") (pintype "bidirectional"))
    )
    (net (code "114") (name "unconnected-(CON1A-IO_B18-PadB18)") (class "Default")
      (node (ref "CON1") (pin "B18") (pinfunction "IO_B18_B18") (pintype "bidirectional"))
    )
    (net (code "115") (name "unconnected-(CON1A-IO_B19-PadB19)") (class "Default")
      (node (ref "CON1") (pin "B19") (pinfunction "IO_B19_B19") (pintype "bidirectional"))
    )
    (net (code "116") (name "unconnected-(CON1A-IO_B20-PadB20)") (class "Default")
      (node (ref "CON1") (pin "B20") (pinfunction "IO_B20_B20") (pintype "bidirectional"))
    )
    (net (code "117") (name "unconnected-(CON1A-IO_B21-PadB21)") (class "Default")
      (node (ref "CON1") (pin "B21") (pinfunction "IO_B21_B21") (pintype "bidirectional"))
    )
    (net (code "118") (name "unconnected-(CON1B-IO_C5-PadC5)") (class "Default")
      (node (ref "CON1") (pin "C5") (pinfunction "IO_C5_C5") (pintype "bidirectional"))
    )
    (net (code "119") (name "unconnected-(CON1B-IO_C6-PadC6)") (class "Default")
      (node (ref "CON1") (pin "C6") (pinfunction "IO_C6_C6") (pintype "bidirectional"))
    )
    (net (code "120") (name "unconnected-(CON1B-IO_C7-PadC7)") (class "Default")
      (node (ref "CON1") (pin "C7") (pinfunction "IO_C7_C7") (pintype "bidirectional"))
    )
    (net (code "121") (name "unconnected-(CON1B-IO_C8-PadC8)") (class "Default")
      (node (ref "CON1") (pin "C8") (pinfunction "IO_C8_C8") (pintype "bidirectional"))
    )
    (net (code "122") (name "unconnected-(CON1B-IO_C9-PadC9)") (class "Default")
      (node (ref "CON1") (pin "C9") (pinfunction "IO_C9_C9") (pintype "bidirectional"))
    )
    (net (code "123") (name "unconnected-(CON1B-IO_C10-PadC10)") (class "Default")
      (node (ref "CON1") (pin "C10") (pinfunction "IO_C10_C10") (pintype "bidirectional"))
    )
    (net (code "124") (name "unconnected-(CON1B-IO_C11-PadC11)") (class "Default")
      (node (ref "CON1") (pin "C11") (pinfunction "IO_C11_C11") (pintype "bidirectional"))
    )
    (net (code "125") (name "unconnected-(CON1B-IO_C12-PadC12)") (class "Default")
      (node (ref "CON1") (pin "C12") (pinfunction "IO_C12_C12") (pintype "bidirectional"))
    )
    (net (code "126") (name "unconnected-(CON1B-IO_C13-PadC13)") (class "Default")
      (node (ref "CON1") (pin "C13") (pinfunction "IO_C13_C13") (pintype "bidirectional"))
    )
    (net (code "127") (name "unconnected-(CON1B-IO_C14-PadC14)") (class "Default")
      (node (ref "CON1") (pin "C14") (pinfunction "IO_C14_C14") (pintype "bidirectional"))
    )
    (net (code "128") (name "unconnected-(CON1B-IO_C15-PadC15)") (class "Default")
      (node (ref "CON1") (pin "C15") (pinfunction "IO_C15_C15") (pintype "bidirectional"))
    )
    (net (code "129") (name "unconnected-(CON1B-IO_C19-PadC19)") (class "Default")
      (node (ref "CON1") (pin "C19") (pinfunction "IO_C19_C19") (pintype "bidirectional"))
    )
    (net (code "130") (name "unconnected-(CON1B-IO_C20-PadC20)") (class "Default")
      (node (ref "CON1") (pin "C20") (pinfunction "IO_C20_C20") (pintype "bidirectional"))
    )
    (net (code "131") (name "unconnected-(CON1B-IO_C21-PadC21)") (class "Default")
      (node (ref "CON1") (pin "C21") (pinfunction "IO_C21_C21") (pintype "bidirectional"))
    )
    (net (code "132") (name "unconnected-(CON1B-IO_C22-PadC22)") (class "Default")
      (node (ref "CON1") (pin "C22") (pinfunction "IO_C22_C22") (pintype "bidirectional"))
    )
    (net (code "133") (name "unconnected-(CON1B-IO_D5-PadD5)") (class "Default")
      (node (ref "CON1") (pin "D5") (pinfunction "IO_D5_D5") (pintype "bidirectional"))
    )
    (net (code "134") (name "unconnected-(CON1B-IO_D6-PadD6)") (class "Default")
      (node (ref "CON1") (pin "D6") (pinfunction "IO_D6_D6") (pintype "bidirectional"))
    )
    (net (code "135") (name "unconnected-(CON1B-IO_D7-PadD7)") (class "Default")
      (node (ref "CON1") (pin "D7") (pinfunction "IO_D7_D7") (pintype "bidirectional"))
    )
    (net (code "136") (name "unconnected-(CON1B-IO_D8-PadD8)") (class "Default")
      (node (ref "CON1") (pin "D8") (pinfunction "IO_D8_D8") (pintype "bidirectional"))
    )
    (net (code "137") (name "unconnected-(CON1B-IO_D9-PadD9)") (class "Default")
      (node (ref "CON1") (pin "D9") (pinfunction "IO_D9_D9") (pintype "bidirectional"))
    )
    (net (code "138") (name "unconnected-(CON1B-IO_D10-PadD10)") (class "Default")
      (node (ref "CON1") (pin "D10") (pinfunction "IO_D10_D10") (pintype "bidirectional"))
    )
    (net (code "139") (name "unconnected-(CON1B-IO_D11-PadD11)") (class "Default")
      (node (ref "CON1") (pin "D11") (pinfunction "IO_D11_D11") (pintype "bidirectional"))
    )
    (net (code "140") (name "unconnected-(CON1B-IO_D12-PadD12)") (class "Default")
      (node (ref "CON1") (pin "D12") (pinfunction "IO_D12_D12") (pintype "bidirectional"))
    )
    (net (code "141") (name "unconnected-(CON1B-IO_D13-PadD13)") (class "Default")
      (node (ref "CON1") (pin "D13") (pinfunction "IO_D13_D13") (pintype "bidirectional"))
    )
    (net (code "142") (name "unconnected-(CON1B-IO_D14-PadD14)") (class "Default")
      (node (ref "CON1") (pin "D14") (pinfunction "IO_D14_D14") (pintype "bidirectional"))
    )
    (net (code "143") (name "unconnected-(CON1B-IO_D15-PadD15)") (class "Default")
      (node (ref "CON1") (pin "D15") (pinfunction "IO_D15_D15") (pintype "bidirectional"))
    )
    (net (code "144") (name "unconnected-(CON1B-IO_D19-PadD19)") (class "Default")
      (node (ref "CON1") (pin "D19") (pinfunction "IO_D19_D19") (pintype "bidirectional"))
    )
    (net (code "145") (name "unconnected-(CON1B-IO_D20-PadD20)") (class "Default")
      (node (ref "CON1") (pin "D20") (pinfunction "IO_D20_D20") (pintype "bidirectional"))
    )
    (net (code "146") (name "unconnected-(CON1B-IO_D21-PadD21)") (class "Default")
      (node (ref "CON1") (pin "D21") (pinfunction "IO_D21_D21") (pintype "bidirectional"))
    )
    (net (code "147") (name "unconnected-(CON1B-RESET_D1-PadD1)") (class "Default")
      (node (ref "CON1") (pin "D1") (pinfunction "RESET_D1_D1") (pintype "bidirectional"))
    )
    (net (code "148") (name "unconnected-(CON1D-3.3V_A15-PadA15)") (class "Default")
      (node (ref "CON1") (pin "A15") (pinfunction "3.3V_A15_A15") (pintype "bidirectional"))
    )
    (net (code "149") (name "unconnected-(CON1D-3.3V_B15-PadB15)") (class "Default")
      (node (ref "CON1") (pin "B15") (pinfunction "3.3V_B15_B15") (pintype "bidirectional"))
    )
    (net (code "150") (name "unconnected-(CON1D-USB_5V_C1-PadC1)") (class "Default")
      (node (ref "CON1") (pin "C1") (pinfunction "USB_5V_C1_C1") (pintype "bidirectional"))
    )
    (net (code "151") (name "unconnected-(CON1D-VCCO_AB_A17-PadA17)") (class "Default")
      (node (ref "CON1") (pin "A17") (pinfunction "VCCO_AB_A17_A17") (pintype "bidirectional"))
    )
    (net (code "152") (name "unconnected-(CON1D-VCCO_AB_B17-PadB17)") (class "Default")
      (node (ref "CON1") (pin "B17") (pinfunction "VCCO_AB_B17_B17") (pintype "bidirectional"))
    )
    (net (code "153") (name "unconnected-(CON1D-VCCO_CD_C16-PadC16)") (class "Default")
      (node (ref "CON1") (pin "C16") (pinfunction "VCCO_CD_C16_C16") (pintype "bidirectional"))
    )
    (net (code "154") (name "unconnected-(CON1D-VCCO_CD_D16-PadD16)") (class "Default")
      (node (ref "CON1") (pin "D16") (pinfunction "VCCO_CD_D16_D16") (pintype "bidirectional"))
    )
    (net (code "155") (name "unconnected-(J1-Pad4)") (class "Default")
      (node (ref "J1") (pin "4") (pinfunction "4_4") (pintype "passive"))
    )
    (net (code "156") (name "unconnected-(J1-Pad20)") (class "Default")
      (node (ref "J1") (pin "20") (pinfunction "20_20") (pintype "passive"))
    )
    (net (code "157") (name "unconnected-(J1-Pad21)") (class "Default")
      (node (ref "J1") (pin "21") (pinfunction "21_21") (pintype "passive"))
    )
    (net (code "158") (name "unconnected-(J1-Pad22)") (class "Default")
      (node (ref "J1") (pin "22") (pinfunction "22_22") (pintype "passive"))
    )
    (net (code "159") (name "unconnected-(J1-Pad28)") (class "Default")
      (node (ref "J1") (pin "28") (pinfunction "28_28") (pintype "passive"))
    )
    (net (code "160") (name "unconnected-(J1-Pad29)") (class "Default")
      (node (ref "J1") (pin "29") (pinfunction "29_29") (pintype "passive"))
    )
    (net (code "161") (name "unconnected-(J1-Pad32)") (class "Default")
      (node (ref "J1") (pin "32") (pinfunction "32_32") (pintype "passive"))
    )
    (net (code "162") (name "unconnected-(J1-Pad33)") (class "Default")
      (node (ref "J1") (pin "33") (pinfunction "33_33") (pintype "passive"))
    )
    (net (code "163") (name "unconnected-(J1-Pad34)") (class "Default")
      (node (ref "J1") (pin "34") (pinfunction "34_34") (pintype "passive"))
    )
    (net (code "164") (name "unconnected-(J1-Pad35)") (class "Default")
      (node (ref "J1") (pin "35") (pinfunction "35_35") (pintype "passive"))
    )
    (net (code "165") (name "unconnected-(J1-Pad36)") (class "Default")
      (node (ref "J1") (pin "36") (pinfunction "36_36") (pintype "passive"))
    )
    (net (code "166") (name "unconnected-(J1-Pad37)") (class "Default")
      (node (ref "J1") (pin "37") (pinfunction "37_37") (pintype "passive"))
    )
    (net (code "167") (name "unconnected-(J1-Pad38)") (class "Default")
      (node (ref "J1") (pin "38") (pinfunction "38_38") (pintype "passive"))
    )
    (net (code "168") (name "unconnected-(J1-Pad39)") (class "Default")
      (node (ref "J1") (pin "39") (pinfunction "39_39") (pintype "passive"))
    )
    (net (code "169") (name "unconnected-(J1-Pad41)") (class "Default")
      (node (ref "J1") (pin "41") (pinfunction "41_41") (pintype "passive"))
    )
    (net (code "170") (name "unconnected-(J1-Pad42)") (class "Default")
      (node (ref "J1") (pin "42") (pinfunction "42_42") (pintype "passive"))
    )
    (net (code "171") (name "unconnected-(J1-Pad43)") (class "Default")
      (node (ref "J1") (pin "43") (pinfunction "43_43") (pintype "passive"))
    )
    (net (code "172") (name "unconnected-(J1-Pad44)") (class "Default")
      (node (ref "J1") (pin "44") (pinfunction "44_44") (pintype "passive"))
    )
    (net (code "173") (name "unconnected-(J1-Pad45)") (class "Default")
      (node (ref "J1") (pin "45") (pinfunction "45_45") (pintype "passive"))
    )
    (net (code "174") (name "unconnected-(J1-Pad46)") (class "Default")
      (node (ref "J1") (pin "46") (pinfunction "46_46") (pintype "passive"))
    )
    (net (code "175") (name "unconnected-(J1-Pad47)") (class "Default")
      (node (ref "J1") (pin "47") (pinfunction "47_47") (pintype "passive"))
    )
    (net (code "176") (name "unconnected-(J1-Pad48)") (class "Default")
      (node (ref "J1") (pin "48") (pinfunction "48_48") (pintype "passive"))
    )
    (net (code "177") (name "unconnected-(J1-Pad49)") (class "Default")
      (node (ref "J1") (pin "49") (pinfunction "49_49") (pintype "passive"))
    )
    (net (code "178") (name "unconnected-(J1-Pad52)") (class "Default")
      (node (ref "J1") (pin "52") (pinfunction "52_52") (pintype "passive"))
    )
    (net (code "179") (name "unconnected-(J1-Pad53)") (class "Default")
      (node (ref "J1") (pin "53") (pinfunction "53_53") (pintype "passive"))
    )
    (net (code "180") (name "unconnected-(J1-Pad54)") (class "Default")
      (node (ref "J1") (pin "54") (pinfunction "54_54") (pintype "passive"))
    )
    (net (code "181") (name "unconnected-(J1-Pad70)") (class "Default")
      (node (ref "J1") (pin "70") (pinfunction "70_70") (pintype "passive"))
    )
    (net (code "182") (name "unconnected-(J1-Pad71)") (class "Default")
      (node (ref "J1") (pin "71") (pinfunction "71_71") (pintype "passive"))
    )
    (net (code "183") (name "unconnected-(J1-Pad72)") (class "Default")
      (node (ref "J1") (pin "72") (pinfunction "72_72") (pintype "passive"))
    )
    (net (code "184") (name "unconnected-(J1-Pad78)") (class "Default")
      (node (ref "J1") (pin "78") (pinfunction "78_78") (pintype "passive"))
    )
    (net (code "185") (name "unconnected-(J1-Pad79)") (class "Default")
      (node (ref "J1") (pin "79") (pinfunction "79_79") (pintype "passive"))
    )
    (net (code "186") (name "unconnected-(J1-Pad82)") (class "Default")
      (node (ref "J1") (pin "82") (pinfunction "82_82") (pintype "passive"))
    )
    (net (code "187") (name "unconnected-(J1-Pad83)") (class "Default")
      (node (ref "J1") (pin "83") (pinfunction "83_83") (pintype "passive"))
    )
    (net (code "188") (name "unconnected-(J1-Pad84)") (class "Default")
      (node (ref "J1") (pin "84") (pinfunction "84_84") (pintype "passive"))
    )
    (net (code "189") (name "unconnected-(J1-Pad85)") (class "Default")
      (node (ref "J1") (pin "85") (pinfunction "85_85") (pintype "passive"))
    )
    (net (code "190") (name "unconnected-(J1-Pad86)") (class "Default")
      (node (ref "J1") (pin "86") (pinfunction "86_86") (pintype "passive"))
    )
    (net (code "191") (name "unconnected-(J1-Pad87)") (class "Default")
      (node (ref "J1") (pin "87") (pinfunction "87_87") (pintype "passive"))
    )
    (net (code "192") (name "unconnected-(J1-Pad88)") (class "Default")
      (node (ref "J1") (pin "88") (pinfunction "88_88") (pintype "passive"))
    )
    (net (code "193") (name "unconnected-(J1-Pad89)") (class "Default")
      (node (ref "J1") (pin "89") (pinfunction "89_89") (pintype "passive"))
    )
    (net (code "194") (name "unconnected-(J1-Pad91)") (class "Default")
      (node (ref "J1") (pin "91") (pinfunction "91_91") (pintype "passive"))
    )
    (net (code "195") (name "unconnected-(J1-Pad92)") (class "Default")
      (node (ref "J1") (pin "92") (pinfunction "92_92") (pintype "passive"))
    )
    (net (code "196") (name "unconnected-(J1-Pad93)") (class "Default")
      (node (ref "J1") (pin "93") (pinfunction "93_93") (pintype "passive"))
    )
    (net (code "197") (name "unconnected-(J1-Pad94)") (class "Default")
      (node (ref "J1") (pin "94") (pinfunction "94_94") (pintype "passive"))
    )
    (net (code "198") (name "unconnected-(J1-Pad95)") (class "Default")
      (node (ref "J1") (pin "95") (pinfunction "95_95") (pintype "passive"))
    )
    (net (code "199") (name "unconnected-(J1-Pad96)") (class "Default")
      (node (ref "J1") (pin "96") (pinfunction "96_96") (pintype "passive"))
    )
    (net (code "200") (name "unconnected-(J1-Pad97)") (class "Default")
      (node (ref "J1") (pin "97") (pinfunction "97_97") (pintype "passive"))
    )
    (net (code "201") (name "unconnected-(J1-Pad98)") (class "Default")
      (node (ref "J1") (pin "98") (pinfunction "98_98") (pintype "passive"))
    )
    (net (code "202") (name "unconnected-(J1-Pad99)") (class "Default")
      (node (ref "J1") (pin "99") (pinfunction "99_99") (pintype "passive"))
    )
    (net (code "203") (name "unconnected-(P1-Pad12)") (class "Default")
      (node (ref "P1") (pin "12") (pinfunction "12_12") (pintype "passive"))
    )
    (net (code "204") (name "unconnected-(P1-Pad14)") (class "Default")
      (node (ref "P1") (pin "14") (pinfunction "14_14") (pintype "passive"))
    )
    (net (code "205") (name "unconnected-(U5-A1-Pad1)") (class "Default")
      (node (ref "U5") (pin "1") (pinfunction "A1_1") (pintype "bidirectional"))
    )
    (net (code "206") (name "unconnected-(U5-A2-Pad3)") (class "Default")
      (node (ref "U5") (pin "3") (pinfunction "A2_3") (pintype "bidirectional"))
    )
    (net (code "207") (name "unconnected-(U5-A3-Pad4)") (class "Default")
      (node (ref "U5") (pin "4") (pinfunction "A3_4") (pintype "bidirectional"))
    )
    (net (code "208") (name "unconnected-(U5-A4-Pad5)") (class "Default")
      (node (ref "U5") (pin "5") (pinfunction "A4_5") (pintype "bidirectional"))
    )
    (net (code "209") (name "unconnected-(U5-B1-Pad20)") (class "Default")
      (node (ref "U5") (pin "20") (pinfunction "B1_20") (pintype "bidirectional"))
    )
    (net (code "210") (name "unconnected-(U5-B2-Pad18)") (class "Default")
      (node (ref "U5") (pin "18") (pinfunction "B2_18") (pintype "bidirectional"))
    )
    (net (code "211") (name "unconnected-(U5-B3-Pad17)") (class "Default")
      (node (ref "U5") (pin "17") (pinfunction "B3_17") (pintype "bidirectional"))
    )
    (net (code "212") (name "unconnected-(U5-B4-Pad16)") (class "Default")
      (node (ref "U5") (pin "16") (pinfunction "B4_16") (pintype "bidirectional"))
    )
  )
)
